# eeZee_big_tiny.net
KiCad netlist of a schematic drawn in EAGLE
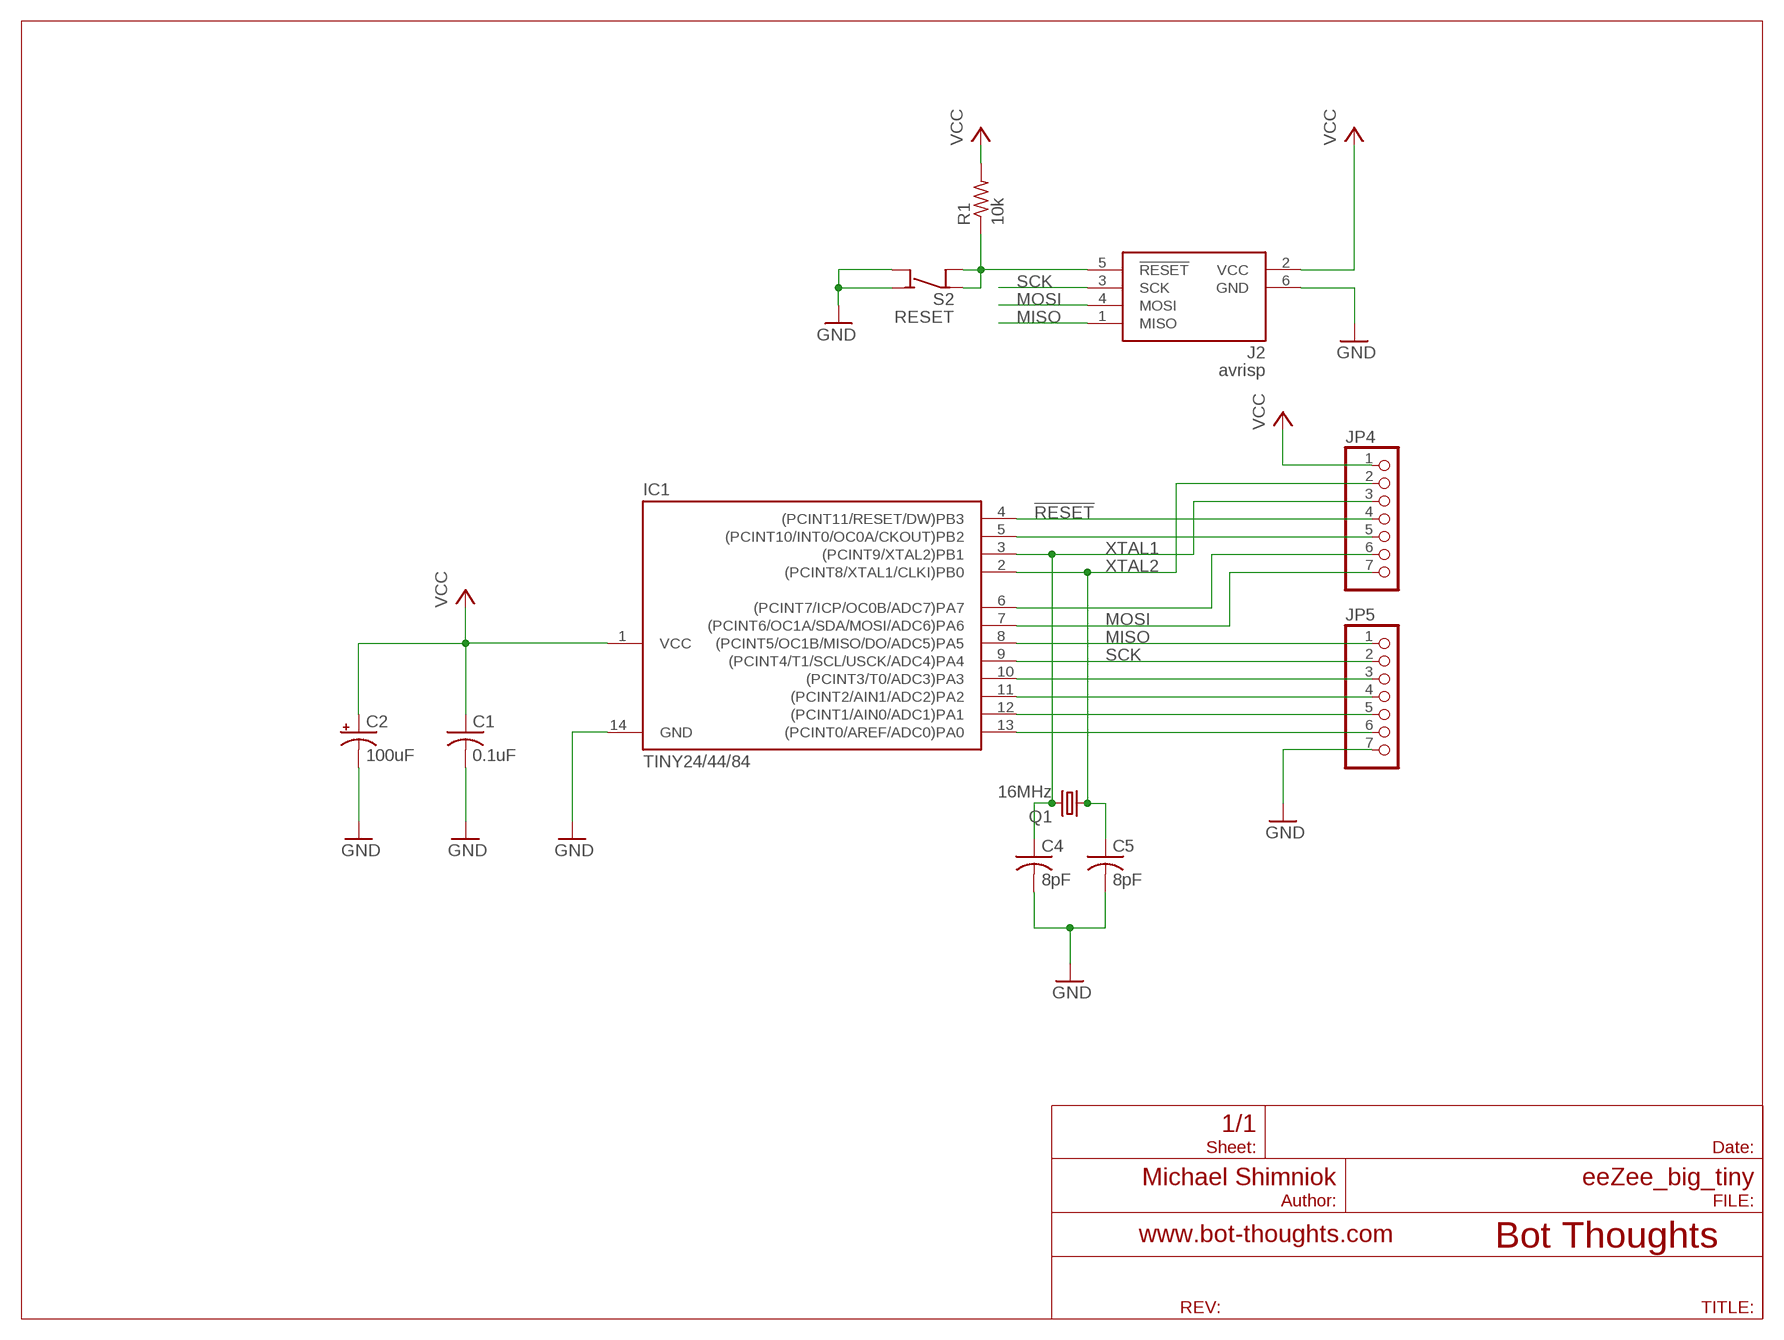
[diagram p0: schematic, sheet 1]

(export (version "E")
  (design (tool "Eeschema 10.0.6"))
  (components
    (comp (ref "C1")
      (value "0.1uF")
      (footprint "eagle-import:C0603")
      (fields (field (name "PARTNO") "0603YC104KAT2A"))
      (libsource (lib "eagle-import") (part "C-USC0603"))
    )
    (comp (ref "C2")
      (value "100uF")
      (footprint "eagle-import:SMC_B")
      (fields (field (name "PARTNO") "MCTT21X106M6R3CT"))
      (libsource (lib "eagle-import") (part "CPOL-USSMCB"))
    )
    (comp (ref "C4")
      (value "8pF")
      (footprint "eagle-import:C0603")
      (fields (field (name "PARTNO") "0603YC104KAT2A"))
      (libsource (lib "eagle-import") (part "C-USC0603"))
    )
    (comp (ref "C5")
      (value "8pF")
      (footprint "eagle-import:C0603")
      (fields (field (name "PARTNO") "0603YC104KAT2A"))
      (libsource (lib "eagle-import") (part "C-USC0603"))
    )
    (comp (ref "IC1")
      (value "TINY24/44/84")
      (footprint "eagle-import:DIL14")
      (libsource (lib "eagle-import") (part "TINY24/44/84-PU"))
    )
    (comp (ref "J2")
      (value "avrisp")
      (footprint "eagle-import:CON6P2R")
      (libsource (lib "eagle-import") (part "AVRISP6"))
    )
    (comp (ref "JP4")
      (value "PINHD-1X07_2.54-S")
      (footprint "eagle-import:1X07-S")
      (libsource (lib "eagle-import") (part "PINHD-1X07_2.54-S"))
    )
    (comp (ref "JP5")
      (value "PINHD-1X07_2.54-S")
      (footprint "eagle-import:1X07-S")
      (libsource (lib "eagle-import") (part "PINHD-1X07_2.54-S"))
    )
    (comp (ref "Q1")
      (value "16MHz")
      (footprint "eagle-import:NDK_2PAD_5X3")
      (libsource (lib "eagle-import") (part "CRYSTALNDK5X3"))
    )
    (comp (ref "R1")
      (value "10k")
      (footprint "eagle-import:R0603")
      (fields (field (name "PARTNO") "ERJ-3GEYJ103V"))
      (libsource (lib "eagle-import") (part "R-US_R0603"))
    )
    (comp (ref "S2")
      (value "RESET")
      (footprint "eagle-import:6MMTACTILE_4PIN")
      (libsource (lib "eagle-import") (part "SPST4"))
    )
  )
  (nets
    (net (code "1") (name "/MISO") (class "Default")
      (node (ref "IC1") (pin "8") (pinfunction "(PCINT5/OC1B/MISO/DO/ADC5)PA5_8") (pintype "bidirectional"))
      (node (ref "J2") (pin "1") (pinfunction "MISO_1") (pintype "input"))
      (node (ref "JP5") (pin "1") (pinfunction "1_1") (pintype "passive"))
    )
    (net (code "2") (name "/MOSI") (class "Default")
      (node (ref "IC1") (pin "7") (pinfunction "(PCINT6/OC1A/SDA/MOSI/ADC6)PA6_7") (pintype "bidirectional"))
      (node (ref "J2") (pin "4") (pinfunction "MOSI_4") (pintype "output"))
      (node (ref "JP4") (pin "7") (pinfunction "7_7") (pintype "passive"))
    )
    (net (code "3") (name "/SCK") (class "Default")
      (node (ref "IC1") (pin "9") (pinfunction "(PCINT4/T1/SCL/USCK/ADC4)PA4_9") (pintype "bidirectional"))
      (node (ref "J2") (pin "3") (pinfunction "SCK_3") (pintype "output"))
      (node (ref "JP5") (pin "2") (pinfunction "2_2") (pintype "passive"))
    )
    (net (code "4") (name "/XTAL1") (class "Default")
      (node (ref "C5") (pin "1") (pinfunction "1_1") (pintype "passive"))
      (node (ref "IC1") (pin "2") (pinfunction "(PCINT8/XTAL1/CLKI)PB0_2") (pintype "bidirectional"))
      (node (ref "JP4") (pin "2") (pinfunction "2_2") (pintype "passive"))
      (node (ref "Q1") (pin "P$1") (pinfunction "1_P$1") (pintype "passive"))
    )
    (net (code "5") (name "/XTAL2") (class "Default")
      (node (ref "C4") (pin "1") (pinfunction "1_1") (pintype "passive"))
      (node (ref "IC1") (pin "3") (pinfunction "(PCINT9/XTAL2)PB1_3") (pintype "bidirectional"))
      (node (ref "JP4") (pin "3") (pinfunction "3_3") (pintype "passive"))
      (node (ref "Q1") (pin "P$2") (pinfunction "2_P$2") (pintype "passive"))
    )
    (net (code "6") (name "/~{RESET}") (class "Default")
      (node (ref "IC1") (pin "4") (pinfunction "(PCINT11/RESET/DW)PB3_4") (pintype "bidirectional"))
      (node (ref "J2") (pin "5") (pinfunction "~{RESET}_5") (pintype "output"))
      (node (ref "JP4") (pin "4") (pinfunction "4_4") (pintype "passive"))
      (node (ref "R1") (pin "1") (pinfunction "1_1") (pintype "passive"))
      (node (ref "S2") (pin "B1") (pinfunction "COM_B1") (pintype "passive"))
      (node (ref "S2") (pin "B2") (pinfunction "COM_B2") (pintype "passive"))
    )
    (net (code "7") (name "GND") (class "Default")
      (node (ref "C1") (pin "2") (pinfunction "2_2") (pintype "passive"))
      (node (ref "C2") (pin "-") (pinfunction "-_-") (pintype "passive"))
      (node (ref "C4") (pin "2") (pinfunction "2_2") (pintype "passive"))
      (node (ref "C5") (pin "2") (pinfunction "2_2") (pintype "passive"))
      (node (ref "IC1") (pin "14") (pinfunction "GND_14") (pintype "power_in"))
      (node (ref "J2") (pin "6") (pinfunction "GND_6") (pintype "power_in"))
      (node (ref "JP5") (pin "7") (pinfunction "7_7") (pintype "passive"))
      (node (ref "S2") (pin "A1") (pinfunction "NO_A1") (pintype "passive"))
      (node (ref "S2") (pin "A2") (pinfunction "NO_A2") (pintype "passive"))
    )
    (net (code "8") (name "Net-(IC1-(PCINT0{slash}AREF{slash}ADC0)PA0)") (class "Default")
      (node (ref "IC1") (pin "13") (pinfunction "(PCINT0/AREF/ADC0)PA0_13") (pintype "bidirectional"))
      (node (ref "JP5") (pin "6") (pinfunction "6_6") (pintype "passive"))
    )
    (net (code "9") (name "Net-(IC1-(PCINT1{slash}AIN0{slash}ADC1)PA1)") (class "Default")
      (node (ref "IC1") (pin "12") (pinfunction "(PCINT1/AIN0/ADC1)PA1_12") (pintype "bidirectional"))
      (node (ref "JP5") (pin "5") (pinfunction "5_5") (pintype "passive"))
    )
    (net (code "10") (name "Net-(IC1-(PCINT2{slash}AIN1{slash}ADC2)PA2)") (class "Default")
      (node (ref "IC1") (pin "11") (pinfunction "(PCINT2/AIN1/ADC2)PA2_11") (pintype "bidirectional"))
      (node (ref "JP5") (pin "4") (pinfunction "4_4") (pintype "passive"))
    )
    (net (code "11") (name "Net-(IC1-(PCINT3{slash}T0{slash}ADC3)PA3)") (class "Default")
      (node (ref "IC1") (pin "10") (pinfunction "(PCINT3/T0/ADC3)PA3_10") (pintype "bidirectional"))
      (node (ref "JP5") (pin "3") (pinfunction "3_3") (pintype "passive"))
    )
    (net (code "12") (name "Net-(IC1-(PCINT7{slash}ICP{slash}OC0B{slash}ADC7)PA7)") (class "Default")
      (node (ref "IC1") (pin "6") (pinfunction "(PCINT7/ICP/OC0B/ADC7)PA7_6") (pintype "bidirectional"))
      (node (ref "JP4") (pin "6") (pinfunction "6_6") (pintype "passive"))
    )
    (net (code "13") (name "Net-(IC1-(PCINT10{slash}INT0{slash}OC0A{slash}CKOUT)PB2)") (class "Default")
      (node (ref "IC1") (pin "5") (pinfunction "(PCINT10/INT0/OC0A/CKOUT)PB2_5") (pintype "bidirectional"))
      (node (ref "JP4") (pin "5") (pinfunction "5_5") (pintype "passive"))
    )
    (net (code "14") (name "VCC") (class "Default")
      (node (ref "C1") (pin "1") (pinfunction "1_1") (pintype "passive"))
      (node (ref "C2") (pin "+") (pinfunction "+_+") (pintype "passive"))
      (node (ref "IC1") (pin "1") (pinfunction "VCC_1") (pintype "power_in"))
      (node (ref "J2") (pin "2") (pinfunction "VCC_2") (pintype "power_in"))
      (node (ref "JP4") (pin "1") (pinfunction "1_1") (pintype "passive"))
      (node (ref "R1") (pin "2") (pinfunction "2_2") (pintype "passive"))
    )
  )
)
